# TCAN337_CANbus_Transceiver.net
KiCad netlist of a schematic drawn in Altium Designer
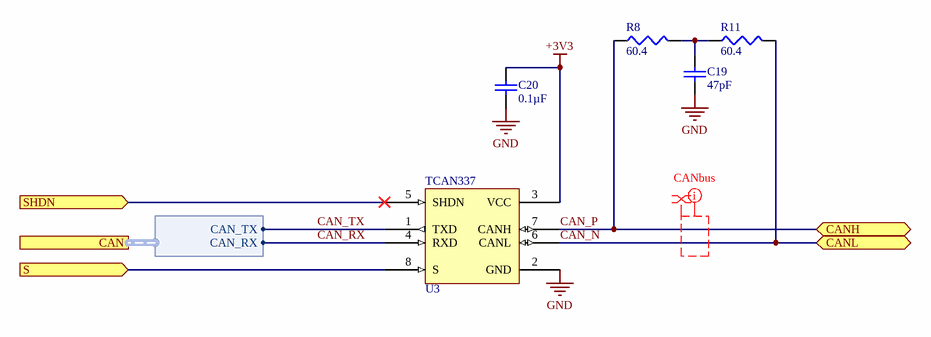
[diagram p0: TCAN337 CANbus Transceiver.SchDoc]

(export (version "E")
  (design (tool "Eeschema 10.0.6"))
  (components
    (comp (ref "C19")
      (value "47pF")
      (footprint "TDK-CGA2B")
      (description "CAP CER 47PF 50V NP0 0402")
      (fields
        (field (name "PART NUMBER") "PC-TDK-01185")
        (field (name "MANUFACTURER PART NUMBER") "CGA2B2NP01H470J050BA")
        (field (name "PUBLISHER") "AlbertaSat")
      )
      (libsource (lib "Database") (part "Cap"))
    )
    (comp (ref "C20")
      (value "0.1µF")
      (footprint "TDK-CGA2B")
      (description "CAP CER 0.1UF 50V X7R 0402")
      (fields
        (field (name "PART NUMBER") "PC-TDK-02259")
        (field (name "MANUFACTURER PART NUMBER") "CGA2B3X7R1H104K050BB")
        (field (name "PUBLISHER") "AlbertaSat")
      )
      (libsource (lib "Database") (part "Cap"))
    )
    (comp (ref "R8")
      (value "60.4")
      (footprint "PANA-ERA2A")
      (description "RES SMD 60.4 OHM 0.1% 1/16W 0402")
      (fields
        (field (name "PART NUMBER") "13829")
        (field (name "MANUFACTURER PART NUMBER") "ERA-2AEB60R4X")
        (field (name "PUBLISHER") "Altium Limited")
      )
      (libsource (lib "Database") (part "Res3"))
    )
    (comp (ref "R11")
      (value "60.4")
      (footprint "PANA-ERA2A")
      (description "RES SMD 60.4 OHM 0.1% 1/16W 0402")
      (fields
        (field (name "PART NUMBER") "13829")
        (field (name "MANUFACTURER PART NUMBER") "ERA-2AEB60R4X")
        (field (name "PUBLISHER") "Altium Limited")
      )
      (libsource (lib "Database") (part "Res3"))
    )
    (comp (ref "U3")
      (value "TCAN337")
      (footprint "TI-R-PDSO-G8")
      (description "IC TXRX CAN 3.3V SOT23-8")
      (fields (field (name "PART NUMBER") "78") (field (name "MANUFACTURER PART NUMBER") "TCAN337GDCNR"))
      (libsource (lib "Database") (part "TCAN337"))
    )
  )
  (nets
    (net (code "2") (name "+3V3") (class "Default")
      (node (ref "C20") (pin "1") (pinfunction "1_1") (pintype "passive"))
      (node (ref "U3") (pin "3") (pinfunction "VCC_3") (pintype "power_in"))
    )
    (net (code "3") (name "/CAN_N") (class "Default")
      (node (ref "R11") (pin "2") (pinfunction "2_2") (pintype "passive"))
      (node (ref "U3") (pin "6") (pinfunction "CANL_6") (pintype "bidirectional"))
    )
    (net (code "4") (name "/CAN_P") (class "Default")
      (node (ref "R8") (pin "1") (pinfunction "1_1") (pintype "passive"))
      (node (ref "U3") (pin "7") (pinfunction "CANH_7") (pintype "bidirectional"))
    )
    (net (code "5") (name "/CAN_RX") (class "Default")
      (node (ref "U3") (pin "4") (pinfunction "RXD_4") (pintype "input"))
    )
    (net (code "6") (name "/CAN_TX") (class "Default")
      (node (ref "U3") (pin "1") (pinfunction "TXD_1") (pintype "output"))
    )
    (net (code "7") (name "/S") (class "Default")
      (node (ref "U3") (pin "8") (pinfunction "S_8") (pintype "input"))
    )
    (net (code "8") (name "/SHDN") (class "Default")
      (node (ref "U3") (pin "5") (pinfunction "SHDN_5") (pintype "input+no_connect"))
    )
    (net (code "10") (name "GND") (class "Default")
      (node (ref "C19") (pin "1") (pinfunction "1_1") (pintype "passive"))
      (node (ref "C20") (pin "2") (pinfunction "2_2") (pintype "passive"))
      (node (ref "U3") (pin "2") (pinfunction "GND_2") (pintype "power_in"))
    )
    (net (code "11") (name "Net-(C19-Pad2)") (class "Default")
      (node (ref "C19") (pin "2") (pinfunction "2_2") (pintype "passive"))
      (node (ref "R11") (pin "1") (pinfunction "1_1") (pintype "passive"))
      (node (ref "R8") (pin "2") (pinfunction "2_2") (pintype "passive"))
    )
  )
)
